# Pure_VCF.net
KiCad netlist of a schematic drawn in EAGLE
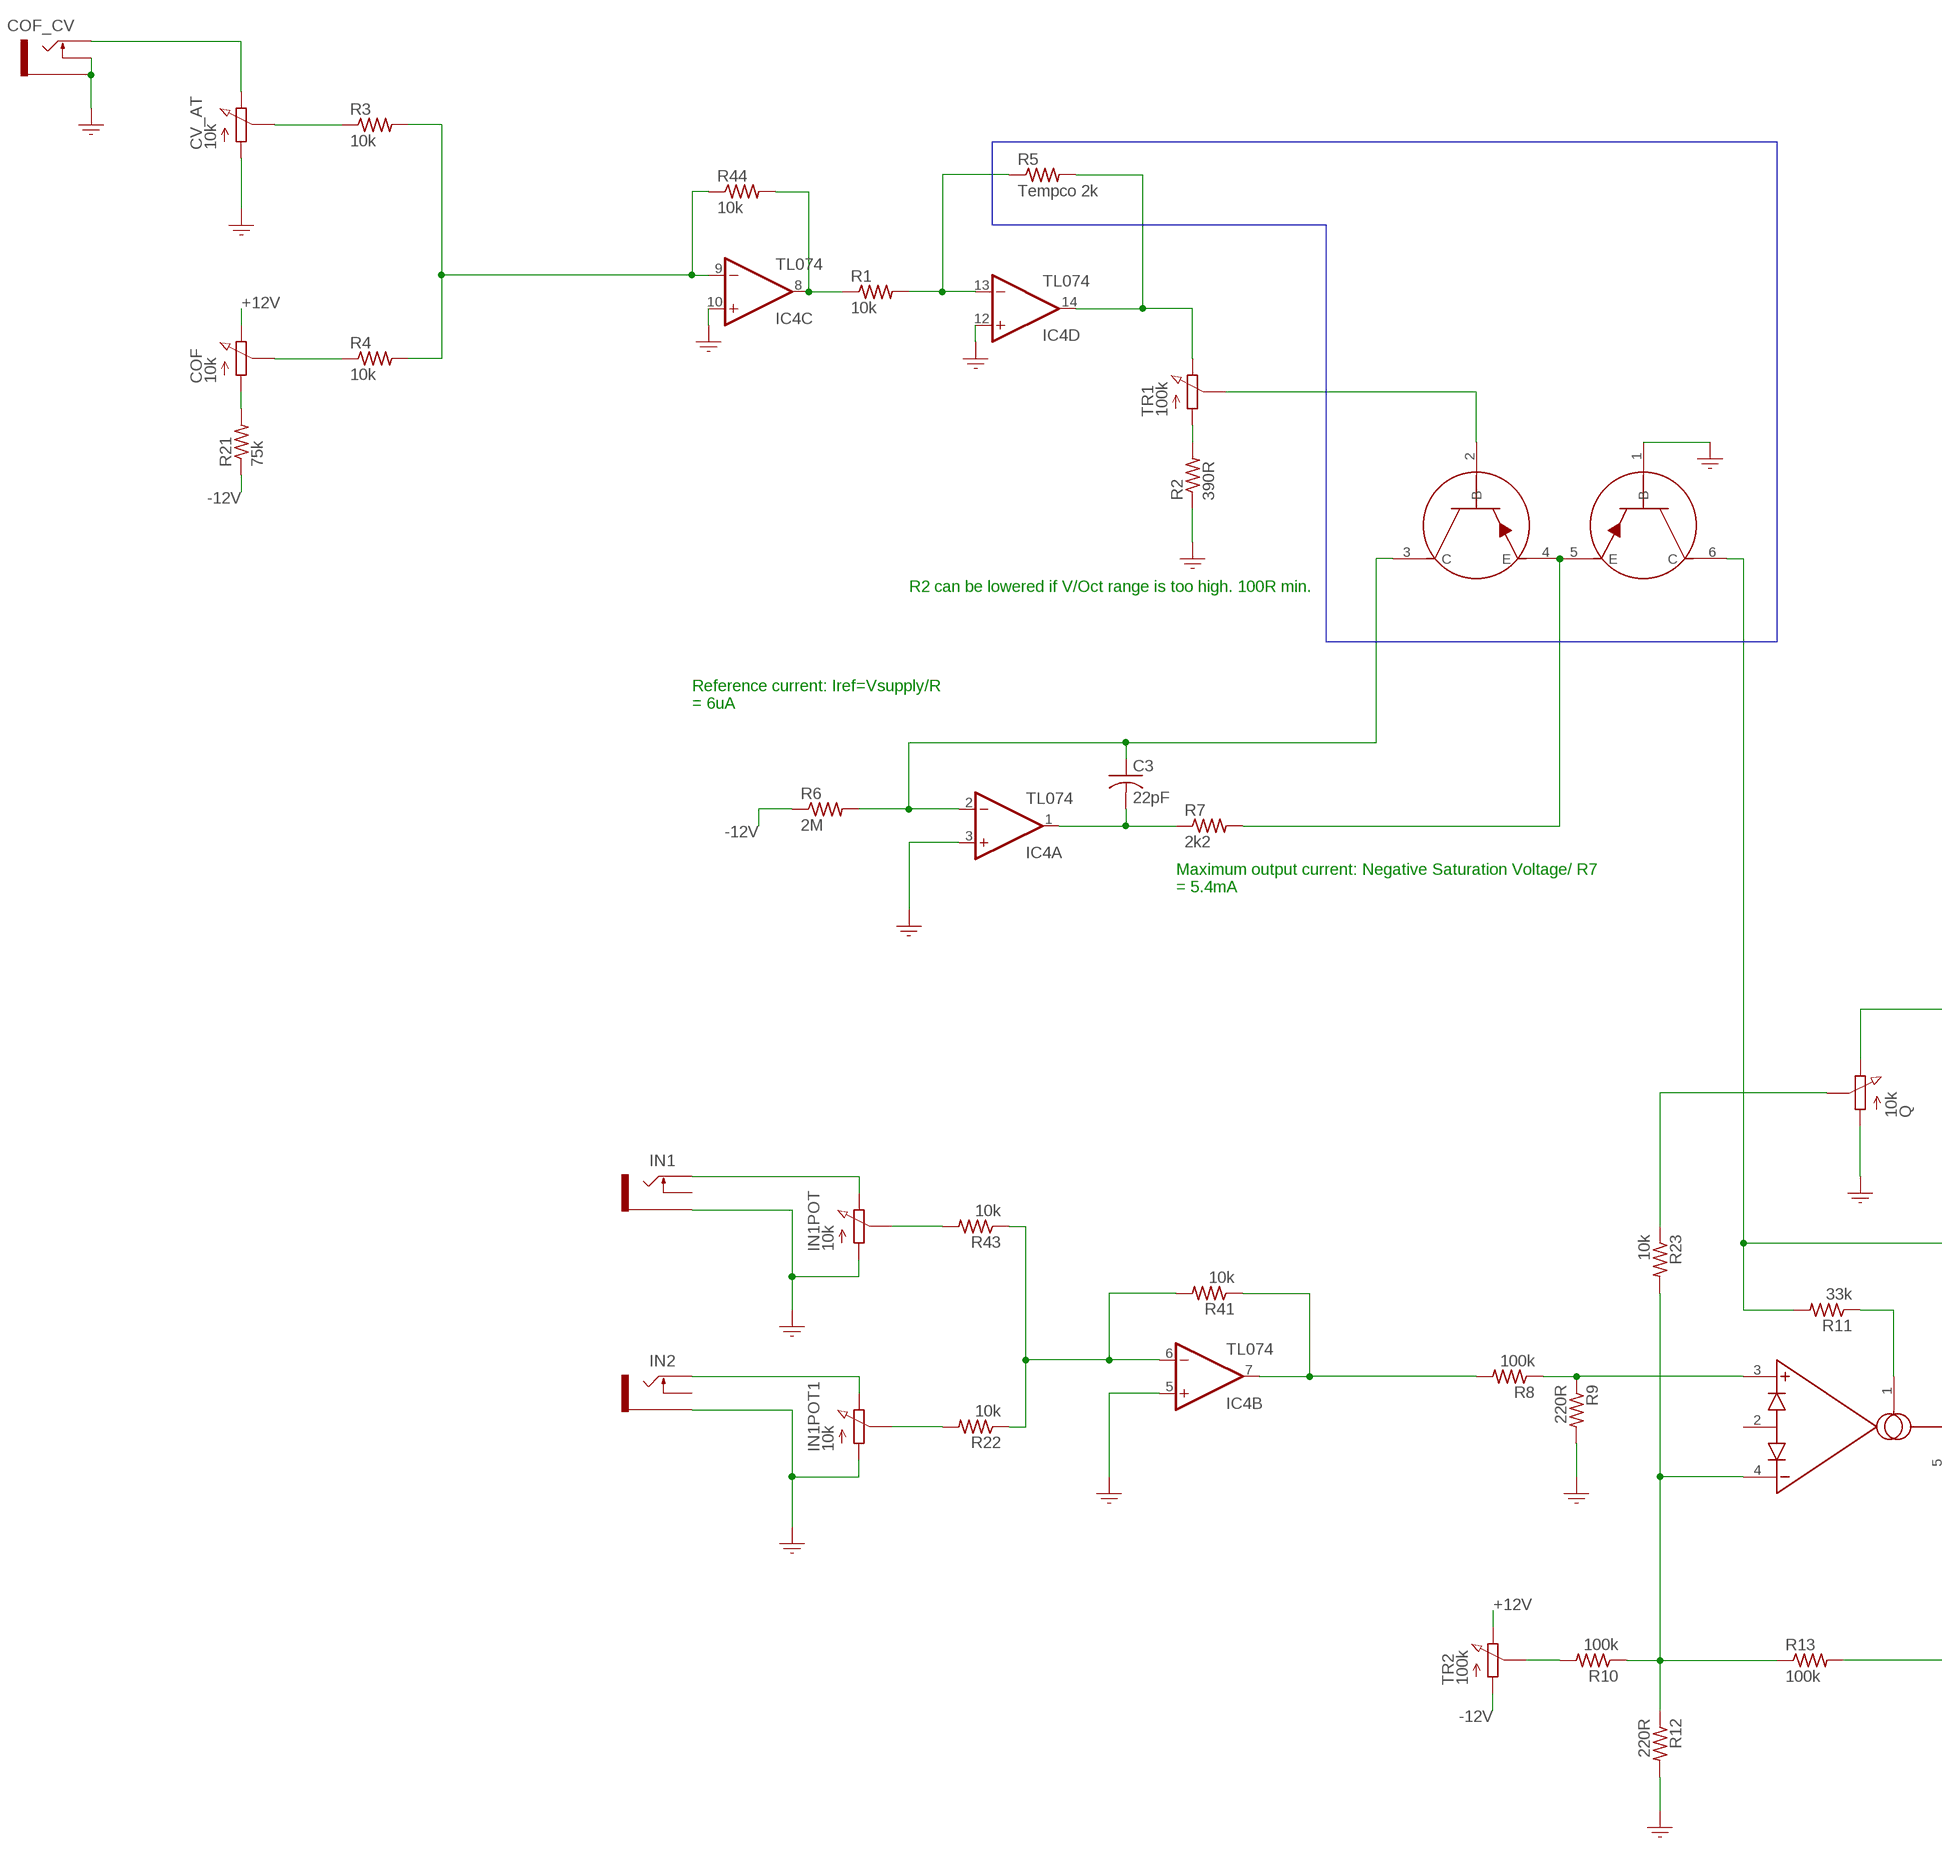
[diagram p0: schematic, sheet 1, part 1 of 2]
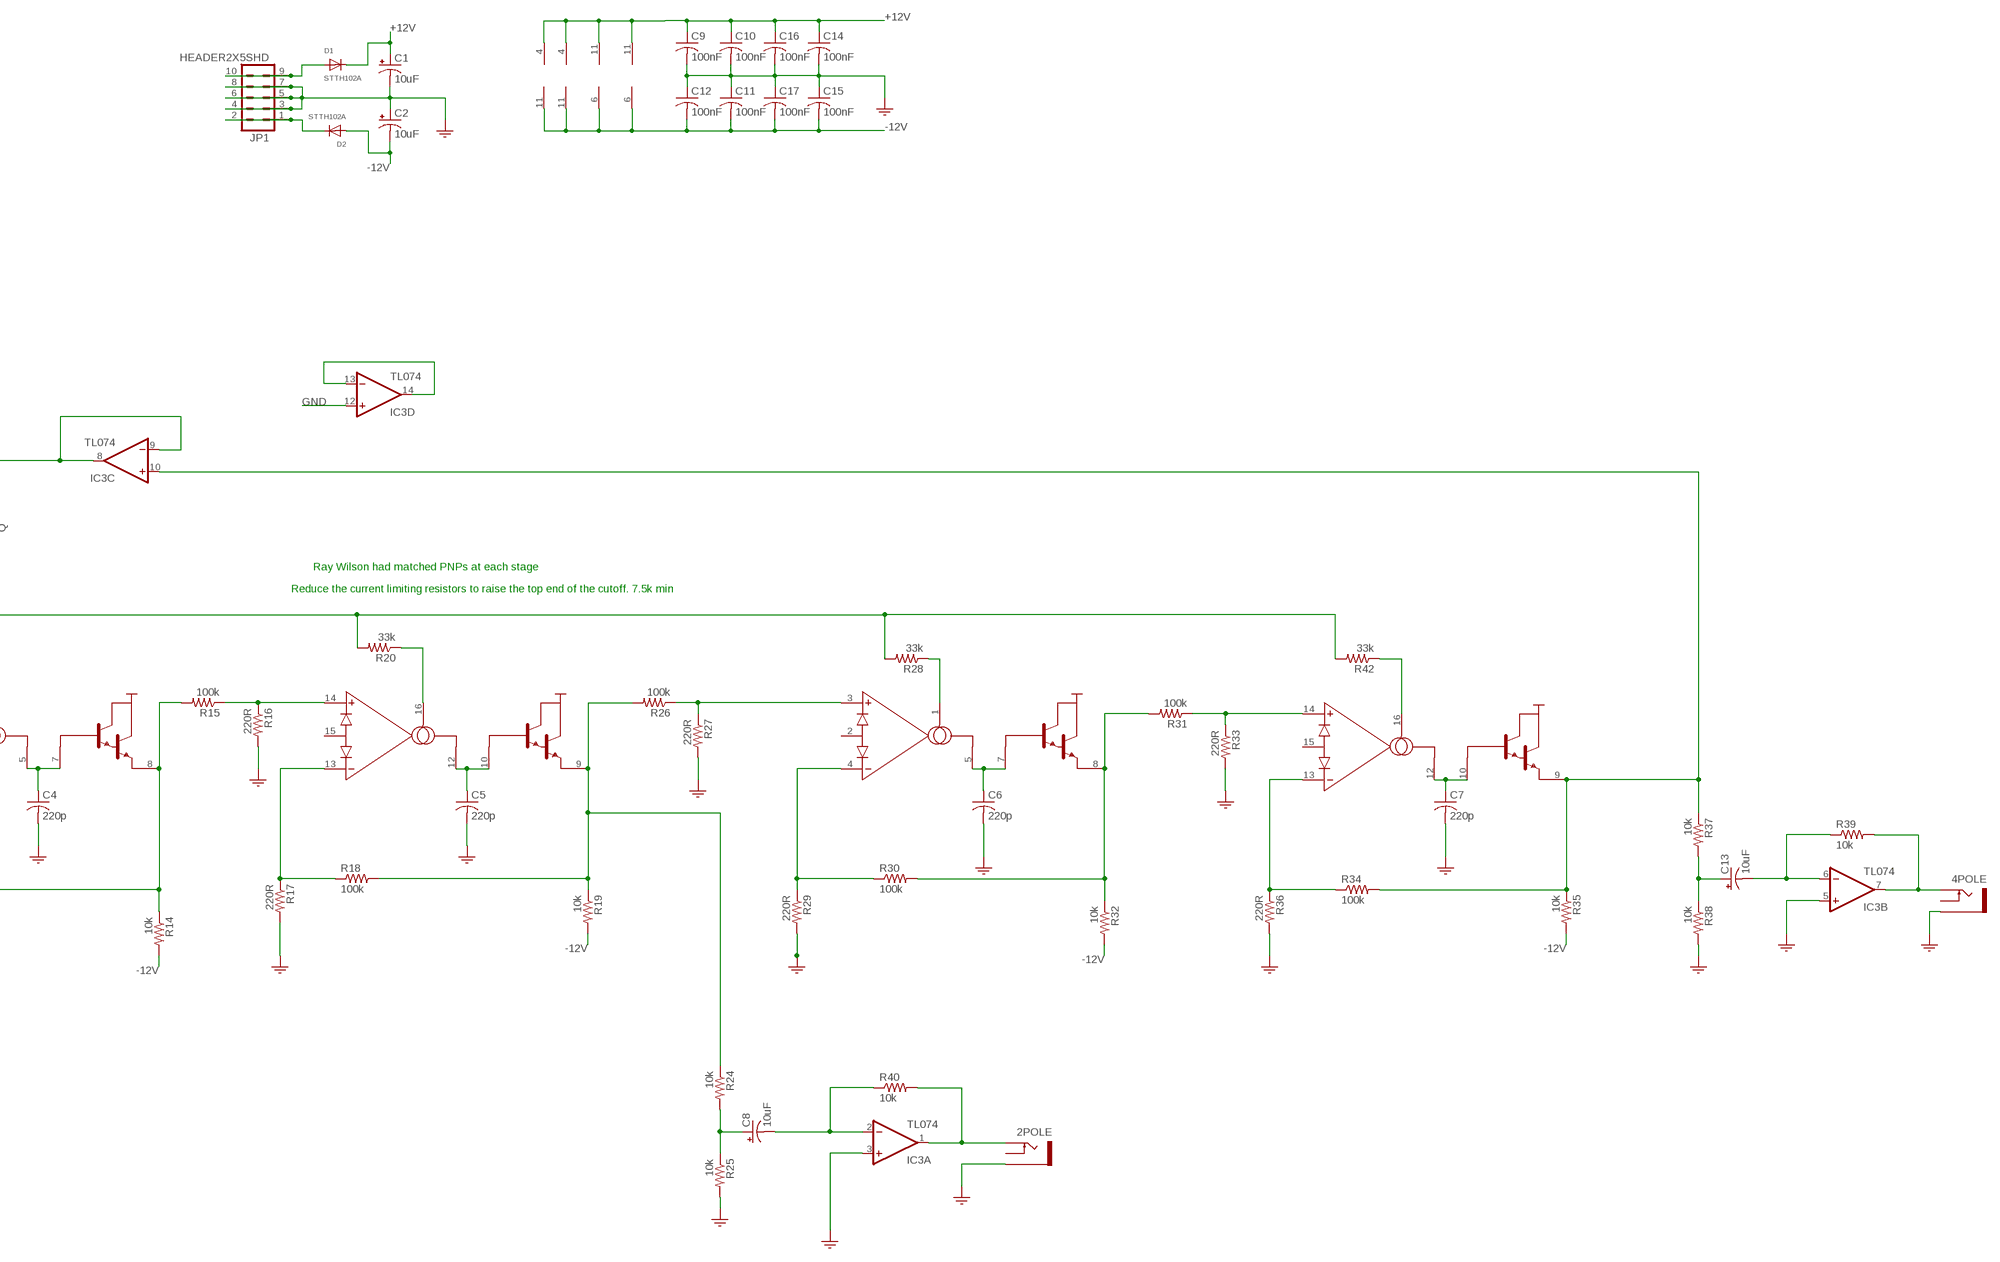
[diagram p1: schematic, sheet 1, part 2 of 2]

(export (version "E")
  (design (tool "Eeschema 10.0.6"))
  (components
    (comp (ref "2POLE")
      (value "PJ301M-12")
      (footprint "eagle-import:PJ301M-12")
      (libsource (lib "eagle-import") (part "SOCKET_MONO_3.5MMPJ301M-12"))
    )
    (comp (ref "4POLE")
      (value "PJ301M-12")
      (footprint "eagle-import:PJ301M-12")
      (libsource (lib "eagle-import") (part "SOCKET_MONO_3.5MMPJ301M-12"))
    )
    (comp (ref "C1")
      (value "10uF")
      (footprint "eagle-import:153CLV-0505")
      (libsource (lib "eagle-import") (part "CAPACITOR_POL-US153CLV-0505"))
    )
    (comp (ref "C2")
      (value "10uF")
      (footprint "eagle-import:153CLV-0505")
      (libsource (lib "eagle-import") (part "CAPACITOR_POL-US153CLV-0505"))
    )
    (comp (ref "C3")
      (value "22pF")
      (footprint "eagle-import:C0805")
      (libsource (lib "eagle-import") (part "CAPACITOR-USC0805"))
    )
    (comp (ref "C4")
      (value "220p")
      (footprint "eagle-import:C050-045X075")
      (libsource (lib "eagle-import") (part "CAPACITOR-USC050-045X075"))
    )
    (comp (ref "C5")
      (value "220p")
      (footprint "eagle-import:C050-045X075")
      (libsource (lib "eagle-import") (part "CAPACITOR-USC050-045X075"))
    )
    (comp (ref "C6")
      (value "220p")
      (footprint "eagle-import:C050-045X075")
      (libsource (lib "eagle-import") (part "CAPACITOR-USC050-045X075"))
    )
    (comp (ref "C7")
      (value "220p")
      (footprint "eagle-import:C050-045X075")
      (libsource (lib "eagle-import") (part "CAPACITOR-USC050-045X075"))
    )
    (comp (ref "C8")
      (value "10uF")
      (footprint "eagle-import:153CLV-0505")
      (libsource (lib "eagle-import") (part "CAPACITOR_POL-US153CLV-0505"))
    )
    (comp (ref "C9")
      (value "100nF")
      (footprint "eagle-import:C0805")
      (libsource (lib "eagle-import") (part "CAPACITOR-USC0805"))
    )
    (comp (ref "C10")
      (value "100nF")
      (footprint "eagle-import:C0805")
      (libsource (lib "eagle-import") (part "CAPACITOR-USC0805"))
    )
    (comp (ref "C11")
      (value "100nF")
      (footprint "eagle-import:C0805")
      (libsource (lib "eagle-import") (part "CAPACITOR-USC0805"))
    )
    (comp (ref "C12")
      (value "100nF")
      (footprint "eagle-import:C0805")
      (libsource (lib "eagle-import") (part "CAPACITOR-USC0805"))
    )
    (comp (ref "C13")
      (value "10uF")
      (footprint "eagle-import:153CLV-0505")
      (libsource (lib "eagle-import") (part "CAPACITOR_POL-US153CLV-0505"))
    )
    (comp (ref "C14")
      (value "100nF")
      (footprint "eagle-import:C0805")
      (libsource (lib "eagle-import") (part "CAPACITOR-USC0805"))
    )
    (comp (ref "C15")
      (value "100nF")
      (footprint "eagle-import:C0805")
      (libsource (lib "eagle-import") (part "CAPACITOR-USC0805"))
    )
    (comp (ref "C16")
      (value "100nF")
      (footprint "eagle-import:C0805")
      (libsource (lib "eagle-import") (part "CAPACITOR-USC0805"))
    )
    (comp (ref "C17")
      (value "100nF")
      (footprint "eagle-import:C0805")
      (libsource (lib "eagle-import") (part "CAPACITOR-USC0805"))
    )
    (comp (ref "COF")
      (value "10k")
      (footprint "eagle-import:POT_9MM_RED_KNOB")
      (libsource (lib "eagle-import") (part "RESISTOR_VARIABLEPOT_9MM_RED_KNOB"))
    )
    (comp (ref "COF_CV")
      (value "PJ301M-12")
      (footprint "eagle-import:PJ301M-12")
      (libsource (lib "eagle-import") (part "SOCKET_MONO_3.5MMPJ301M-12"))
    )
    (comp (ref "CV_AT")
      (value "10k")
      (footprint "eagle-import:POT_9MM_GREEN_KNOB")
      (libsource (lib "eagle-import") (part "RESISTOR_VARIABLEPOT_9MM_GREEN_KNOB"))
    )
    (comp (ref "D1")
      (value "STTH102A")
      (footprint "eagle-import:SMADIODE")
      (libsource (lib "eagle-import") (part "DIODESMA"))
    )
    (comp (ref "D2")
      (value "STTH102A")
      (footprint "eagle-import:SMADIODE")
      (libsource (lib "eagle-import") (part "DIODESMA"))
    )
    (comp (ref "IC1")
      (value "LM13700")
      (footprint "eagle-import:SOIC-16_BLANK")
      (libsource (lib "eagle-import") (part "OTA_LM13700"))
    )
    (comp (ref "IC2")
      (value "LM13700")
      (footprint "eagle-import:SOIC-16_BLANK")
      (libsource (lib "eagle-import") (part "OTA_LM13700"))
    )
    (comp (ref "IC3")
      (value "TL074")
      (footprint "eagle-import:SO14")
      (libsource (lib "eagle-import") (part "OPAMP_QUADD"))
    )
    (comp (ref "IC4")
      (value "TL074")
      (footprint "eagle-import:SO14")
      (libsource (lib "eagle-import") (part "OPAMP_QUADD"))
    )
    (comp (ref "IN1")
      (value "PJ301M-12")
      (footprint "eagle-import:PJ301M-12")
      (libsource (lib "eagle-import") (part "SOCKET_MONO_3.5MMPJ301M-12"))
    )
    (comp (ref "IN1POT")
      (value "10k")
      (footprint "eagle-import:POT_9MM_BLUE_KNOB")
      (libsource (lib "eagle-import") (part "RESISTOR_VARIABLEPOT_9MM_BLUE_KNOB"))
    )
    (comp (ref "IN1POT1")
      (value "10k")
      (footprint "eagle-import:POT_9MM_BLUE_KNOB")
      (libsource (lib "eagle-import") (part "RESISTOR_VARIABLEPOT_9MM_BLUE_KNOB"))
    )
    (comp (ref "IN2")
      (value "PJ301M-12")
      (footprint "eagle-import:PJ301M-12")
      (libsource (lib "eagle-import") (part "SOCKET_MONO_3.5MMPJ301M-12"))
    )
    (comp (ref "JP1")
      (value "HEADER2X5SHD")
      (footprint "eagle-import:2X5-SHROUDED")
      (libsource (lib "eagle-import") (part "HEADER2X5SHD"))
    )
    (comp (ref "Q")
      (value "10k")
      (footprint "eagle-import:POT_9MM_YELLOW_KNOB")
      (libsource (lib "eagle-import") (part "RESISTOR_VARIABLEPOT_9MM_YELLOW_KNOB"))
    )
    (comp (ref "R1")
      (value "10k")
      (footprint "eagle-import:R0805")
      (libsource (lib "eagle-import") (part "RESISTOR_USR0805"))
    )
    (comp (ref "R2")
      (value "390R")
      (footprint "eagle-import:R0805")
      (libsource (lib "eagle-import") (part "RESISTOR_USR0805"))
    )
    (comp (ref "R3")
      (value "10k")
      (footprint "eagle-import:R0805")
      (libsource (lib "eagle-import") (part "RESISTOR_USR0805"))
    )
    (comp (ref "R4")
      (value "10k")
      (footprint "eagle-import:R0805")
      (libsource (lib "eagle-import") (part "RESISTOR_USR0805"))
    )
    (comp (ref "R5")
      (value "Tempco 2k")
      (footprint "eagle-import:0207_8.5")
      (libsource (lib "eagle-import") (part "RESISTOR_US0207/8.5"))
    )
    (comp (ref "R6")
      (value "2M")
      (footprint "eagle-import:R0805")
      (libsource (lib "eagle-import") (part "RESISTOR_USR0805"))
    )
    (comp (ref "R7")
      (value "2k2")
      (footprint "eagle-import:R0805")
      (libsource (lib "eagle-import") (part "RESISTOR_USR0805"))
    )
    (comp (ref "R8")
      (value "100k")
      (footprint "eagle-import:R0805")
      (libsource (lib "eagle-import") (part "RESISTOR_USR0805"))
    )
    (comp (ref "R9")
      (value "220R")
      (footprint "eagle-import:R0805")
      (libsource (lib "eagle-import") (part "RESISTOR_USR0805"))
    )
    (comp (ref "R10")
      (value "100k")
      (footprint "eagle-import:R0805")
      (libsource (lib "eagle-import") (part "RESISTOR_USR0805"))
    )
    (comp (ref "R11")
      (value "33k")
      (footprint "eagle-import:R0805")
      (libsource (lib "eagle-import") (part "RESISTOR_USR0805"))
    )
    (comp (ref "R12")
      (value "220R")
      (footprint "eagle-import:R0805")
      (libsource (lib "eagle-import") (part "RESISTOR_USR0805"))
    )
    (comp (ref "R13")
      (value "100k")
      (footprint "eagle-import:R0805")
      (libsource (lib "eagle-import") (part "RESISTOR_USR0805"))
    )
    (comp (ref "R14")
      (value "10k")
      (footprint "eagle-import:R0805")
      (libsource (lib "eagle-import") (part "RESISTOR_USR0805"))
    )
    (comp (ref "R15")
      (value "100k")
      (footprint "eagle-import:R0805")
      (libsource (lib "eagle-import") (part "RESISTOR_USR0805"))
    )
    (comp (ref "R16")
      (value "220R")
      (footprint "eagle-import:R0805")
      (libsource (lib "eagle-import") (part "RESISTOR_USR0805"))
    )
    (comp (ref "R17")
      (value "220R")
      (footprint "eagle-import:R0805")
      (libsource (lib "eagle-import") (part "RESISTOR_USR0805"))
    )
    (comp (ref "R18")
      (value "100k")
      (footprint "eagle-import:R0805")
      (libsource (lib "eagle-import") (part "RESISTOR_USR0805"))
    )
    (comp (ref "R19")
      (value "10k")
      (footprint "eagle-import:R0805")
      (libsource (lib "eagle-import") (part "RESISTOR_USR0805"))
    )
    (comp (ref "R20")
      (value "33k")
      (footprint "eagle-import:R0805")
      (libsource (lib "eagle-import") (part "RESISTOR_USR0805"))
    )
    (comp (ref "R21")
      (value "75k")
      (footprint "eagle-import:R0805")
      (libsource (lib "eagle-import") (part "RESISTOR_USR0805"))
    )
    (comp (ref "R22")
      (value "10k")
      (footprint "eagle-import:R0805")
      (libsource (lib "eagle-import") (part "RESISTOR_USR0805"))
    )
    (comp (ref "R23")
      (value "10k")
      (footprint "eagle-import:R0805")
      (libsource (lib "eagle-import") (part "RESISTOR_USR0805"))
    )
    (comp (ref "R24")
      (value "10k")
      (footprint "eagle-import:R0805")
      (libsource (lib "eagle-import") (part "RESISTOR_USR0805"))
    )
    (comp (ref "R25")
      (value "10k")
      (footprint "eagle-import:R0805")
      (libsource (lib "eagle-import") (part "RESISTOR_USR0805"))
    )
    (comp (ref "R26")
      (value "100k")
      (footprint "eagle-import:R0805")
      (libsource (lib "eagle-import") (part "RESISTOR_USR0805"))
    )
    (comp (ref "R27")
      (value "220R")
      (footprint "eagle-import:R0805")
      (libsource (lib "eagle-import") (part "RESISTOR_USR0805"))
    )
    (comp (ref "R28")
      (value "33k")
      (footprint "eagle-import:R0805")
      (libsource (lib "eagle-import") (part "RESISTOR_USR0805"))
    )
    (comp (ref "R29")
      (value "220R")
      (footprint "eagle-import:R0805")
      (libsource (lib "eagle-import") (part "RESISTOR_USR0805"))
    )
    (comp (ref "R30")
      (value "100k")
      (footprint "eagle-import:R0805")
      (libsource (lib "eagle-import") (part "RESISTOR_USR0805"))
    )
    (comp (ref "R31")
      (value "100k")
      (footprint "eagle-import:R0805")
      (libsource (lib "eagle-import") (part "RESISTOR_USR0805"))
    )
    (comp (ref "R32")
      (value "10k")
      (footprint "eagle-import:R0805")
      (libsource (lib "eagle-import") (part "RESISTOR_USR0805"))
    )
    (comp (ref "R33")
      (value "220R")
      (footprint "eagle-import:R0805")
      (libsource (lib "eagle-import") (part "RESISTOR_USR0805"))
    )
    (comp (ref "R34")
      (value "100k")
      (footprint "eagle-import:R0805")
      (libsource (lib "eagle-import") (part "RESISTOR_USR0805"))
    )
    (comp (ref "R35")
      (value "10k")
      (footprint "eagle-import:R0805")
      (libsource (lib "eagle-import") (part "RESISTOR_USR0805"))
    )
    (comp (ref "R36")
      (value "220R")
      (footprint "eagle-import:R0805")
      (libsource (lib "eagle-import") (part "RESISTOR_USR0805"))
    )
    (comp (ref "R37")
      (value "10k")
      (footprint "eagle-import:R0805")
      (libsource (lib "eagle-import") (part "RESISTOR_USR0805"))
    )
    (comp (ref "R38")
      (value "10k")
      (footprint "eagle-import:R0805")
      (libsource (lib "eagle-import") (part "RESISTOR_USR0805"))
    )
    (comp (ref "R39")
      (value "10k")
      (footprint "eagle-import:R0805")
      (libsource (lib "eagle-import") (part "RESISTOR_USR0805"))
    )
    (comp (ref "R40")
      (value "10k")
      (footprint "eagle-import:R0805")
      (libsource (lib "eagle-import") (part "RESISTOR_USR0805"))
    )
    (comp (ref "R41")
      (value "10k")
      (footprint "eagle-import:R0805")
      (libsource (lib "eagle-import") (part "RESISTOR_USR0805"))
    )
    (comp (ref "R42")
      (value "33k")
      (footprint "eagle-import:R0805")
      (libsource (lib "eagle-import") (part "RESISTOR_USR0805"))
    )
    (comp (ref "R43")
      (value "10k")
      (footprint "eagle-import:R0805")
      (libsource (lib "eagle-import") (part "RESISTOR_USR0805"))
    )
    (comp (ref "R44")
      (value "10k")
      (footprint "eagle-import:R0805")
      (libsource (lib "eagle-import") (part "RESISTOR_USR0805"))
    )
    (comp (ref "T1")
      (value "DMMT3906W")
      (footprint "eagle-import:TRANS_PAIR")
      (libsource (lib "eagle-import") (part "TRANSISTOR_PAIR_PNP"))
    )
    (comp (ref "TR1")
      (value "100k")
      (footprint "eagle-import:TRIMMER_TH")
      (libsource (lib "eagle-import") (part "RESISTOR_VARIABLETRIMMER_TH"))
    )
    (comp (ref "TR2")
      (value "100k")
      (footprint "eagle-import:TRIMMER_TH")
      (libsource (lib "eagle-import") (part "RESISTOR_VARIABLETRIMMER_TH"))
    )
  )
  (nets
    (net (code "1") (name "/+12V") (class "Default")
      (node (ref "C1") (pin "+") (pinfunction "+_+") (pintype "passive"))
      (node (ref "C10") (pin "1") (pinfunction "1_1") (pintype "passive"))
      (node (ref "C14") (pin "1") (pinfunction "1_1") (pintype "passive"))
      (node (ref "C16") (pin "1") (pinfunction "1_1") (pintype "passive"))
      (node (ref "C9") (pin "1") (pinfunction "1_1") (pintype "passive"))
      (node (ref "COF") (pin "P$3") (pinfunction "3_P$3") (pintype "passive"))
      (node (ref "D1") (pin "C") (pinfunction "C_C") (pintype "passive"))
      (node (ref "IC1") (pin "11") (pinfunction "V+_11") (pintype "power_in"))
      (node (ref "IC2") (pin "11") (pinfunction "V+_11") (pintype "power_in"))
      (node (ref "IC3") (pin "4") (pinfunction "V+_4") (pintype "power_in"))
      (node (ref "IC4") (pin "4") (pinfunction "V+_4") (pintype "power_in"))
      (node (ref "TR2") (pin "3") (pinfunction "3_3") (pintype "passive"))
    )
    (net (code "2") (name "/-12V") (class "Default")
      (node (ref "C11") (pin "2") (pinfunction "2_2") (pintype "passive"))
      (node (ref "C12") (pin "2") (pinfunction "2_2") (pintype "passive"))
      (node (ref "C15") (pin "2") (pinfunction "2_2") (pintype "passive"))
      (node (ref "C17") (pin "2") (pinfunction "2_2") (pintype "passive"))
      (node (ref "C2") (pin "-") (pinfunction "-_-") (pintype "passive"))
      (node (ref "D2") (pin "A") (pinfunction "A_A") (pintype "passive"))
      (node (ref "IC1") (pin "6") (pinfunction "V-_6") (pintype "power_in"))
      (node (ref "IC2") (pin "6") (pinfunction "V-_6") (pintype "power_in"))
      (node (ref "IC3") (pin "11") (pinfunction "V-_11") (pintype "power_in"))
      (node (ref "IC4") (pin "11") (pinfunction "V-_11") (pintype "power_in"))
      (node (ref "R14") (pin "2") (pinfunction "2_2") (pintype "passive"))
      (node (ref "R19") (pin "2") (pinfunction "2_2") (pintype "passive"))
      (node (ref "R21") (pin "1") (pinfunction "1_1") (pintype "passive"))
      (node (ref "R32") (pin "2") (pinfunction "2_2") (pintype "passive"))
      (node (ref "R35") (pin "2") (pinfunction "2_2") (pintype "passive"))
      (node (ref "R6") (pin "1") (pinfunction "1_1") (pintype "passive"))
      (node (ref "TR2") (pin "1") (pinfunction "1_1") (pintype "passive"))
    )
    (net (code "3") (name "GND") (class "Default")
      (node (ref "2POLE") (pin "GND") (pinfunction "SLEEVE_GND") (pintype "passive"))
      (node (ref "4POLE") (pin "GND") (pinfunction "SLEEVE_GND") (pintype "passive"))
      (node (ref "C1") (pin "-") (pinfunction "-_-") (pintype "passive"))
      (node (ref "C10") (pin "2") (pinfunction "2_2") (pintype "passive"))
      (node (ref "C11") (pin "1") (pinfunction "1_1") (pintype "passive"))
      (node (ref "C12") (pin "1") (pinfunction "1_1") (pintype "passive"))
      (node (ref "C14") (pin "2") (pinfunction "2_2") (pintype "passive"))
      (node (ref "C15") (pin "1") (pinfunction "1_1") (pintype "passive"))
      (node (ref "C16") (pin "2") (pinfunction "2_2") (pintype "passive"))
      (node (ref "C17") (pin "1") (pinfunction "1_1") (pintype "passive"))
      (node (ref "C2") (pin "+") (pinfunction "+_+") (pintype "passive"))
      (node (ref "C4") (pin "2") (pinfunction "2_2") (pintype "passive"))
      (node (ref "C5") (pin "2") (pinfunction "2_2") (pintype "passive"))
      (node (ref "C6") (pin "2") (pinfunction "2_2") (pintype "passive"))
      (node (ref "C7") (pin "2") (pinfunction "2_2") (pintype "passive"))
      (node (ref "C9") (pin "2") (pinfunction "2_2") (pintype "passive"))
      (node (ref "COF_CV") (pin "GND") (pinfunction "SLEEVE_GND") (pintype "passive"))
      (node (ref "COF_CV") (pin "NORM") (pinfunction "SWITCH_NORM") (pintype "passive"))
      (node (ref "CV_AT") (pin "P$1") (pinfunction "1_P$1") (pintype "passive"))
      (node (ref "IC3") (pin "12") (pinfunction "+IN_12") (pintype "input"))
      (node (ref "IC3") (pin "3") (pinfunction "+IN_3") (pintype "input"))
      (node (ref "IC3") (pin "5") (pinfunction "+IN_5") (pintype "input"))
      (node (ref "IC4") (pin "10") (pinfunction "+IN_10") (pintype "input"))
      (node (ref "IC4") (pin "12") (pinfunction "+IN_12") (pintype "input"))
      (node (ref "IC4") (pin "3") (pinfunction "+IN_3") (pintype "input"))
      (node (ref "IC4") (pin "5") (pinfunction "+IN_5") (pintype "input"))
      (node (ref "IN1") (pin "GND") (pinfunction "SLEEVE_GND") (pintype "passive"))
      (node (ref "IN1POT") (pin "P$1") (pinfunction "1_P$1") (pintype "passive"))
      (node (ref "IN1POT1") (pin "P$1") (pinfunction "1_P$1") (pintype "passive"))
      (node (ref "IN2") (pin "GND") (pinfunction "SLEEVE_GND") (pintype "passive"))
      (node (ref "JP1") (pin "3") (pinfunction "3_3") (pintype "passive"))
      (node (ref "JP1") (pin "4") (pinfunction "4_4") (pintype "passive"))
      (node (ref "JP1") (pin "5") (pinfunction "5_5") (pintype "passive"))
      (node (ref "JP1") (pin "6") (pinfunction "6_6") (pintype "passive"))
      (node (ref "JP1") (pin "7") (pinfunction "7_7") (pintype "passive"))
      (node (ref "JP1") (pin "8") (pinfunction "8_8") (pintype "passive"))
      (node (ref "Q") (pin "P$1") (pinfunction "1_P$1") (pintype "passive"))
      (node (ref "R12") (pin "2") (pinfunction "2_2") (pintype "passive"))
      (node (ref "R16") (pin "2") (pinfunction "2_2") (pintype "passive"))
      (node (ref "R17") (pin "2") (pinfunction "2_2") (pintype "passive"))
      (node (ref "R2") (pin "1") (pinfunction "1_1") (pintype "passive"))
      (node (ref "R25") (pin "2") (pinfunction "2_2") (pintype "passive"))
      (node (ref "R27") (pin "2") (pinfunction "2_2") (pintype "passive"))
      (node (ref "R29") (pin "2") (pinfunction "2_2") (pintype "passive"))
      (node (ref "R33") (pin "2") (pinfunction "2_2") (pintype "passive"))
      (node (ref "R36") (pin "2") (pinfunction "2_2") (pintype "passive"))
      (node (ref "R38") (pin "2") (pinfunction "2_2") (pintype "passive"))
      (node (ref "R9") (pin "2") (pinfunction "2_2") (pintype "passive"))
      (node (ref "T1") (pin "1") (pinfunction "B_1") (pintype "bidirectional"))
    )
    (net (code "4") (name "Net-(C8-Pad+)") (class "Default")
      (node (ref "C8") (pin "+") (pinfunction "+_+") (pintype "passive"))
      (node (ref "R24") (pin "2") (pinfunction "2_2") (pintype "passive"))
      (node (ref "R25") (pin "1") (pinfunction "1_1") (pintype "passive"))
    )
    (net (code "5") (name "Net-(C13-Pad+)") (class "Default")
      (node (ref "C13") (pin "+") (pinfunction "+_+") (pintype "passive"))
      (node (ref "R37") (pin "2") (pinfunction "2_2") (pintype "passive"))
      (node (ref "R38") (pin "1") (pinfunction "1_1") (pintype "passive"))
    )
    (net (code "6") (name "Net-(COF-1)") (class "Default")
      (node (ref "COF") (pin "P$1") (pinfunction "1_P$1") (pintype "passive"))
      (node (ref "R21") (pin "2") (pinfunction "2_2") (pintype "passive"))
    )
    (net (code "7") (name "Net-(COF-2)") (class "Default")
      (node (ref "COF") (pin "P$2") (pinfunction "2_P$2") (pintype "passive"))
      (node (ref "R4") (pin "1") (pinfunction "1_1") (pintype "passive"))
    )
    (net (code "8") (name "Net-(CV_AT-2)") (class "Default")
      (node (ref "CV_AT") (pin "P$2") (pinfunction "2_P$2") (pintype "passive"))
      (node (ref "R3") (pin "1") (pinfunction "1_1") (pintype "passive"))
    )
    (net (code "9") (name "Net-(CV_AT-3)") (class "Default")
      (node (ref "COF_CV") (pin "TIP") (pinfunction "TIP_TIP") (pintype "passive"))
      (node (ref "CV_AT") (pin "P$3") (pinfunction "3_P$3") (pintype "passive"))
    )
    (net (code "10") (name "Net-(D1-PadA)") (class "Default")
      (node (ref "D1") (pin "A") (pinfunction "A_A") (pintype "passive"))
      (node (ref "JP1") (pin "10") (pinfunction "10_10") (pintype "passive"))
      (node (ref "JP1") (pin "9") (pinfunction "9_9") (pintype "passive"))
    )
    (net (code "11") (name "Net-(D2-PadC)") (class "Default")
      (node (ref "D2") (pin "C") (pinfunction "C_C") (pintype "passive"))
      (node (ref "JP1") (pin "1") (pinfunction "1_1") (pintype "passive"))
      (node (ref "JP1") (pin "2") (pinfunction "2_2") (pintype "passive"))
    )
    (net (code "12") (name "Net-(IC1A-BIAS-IN)") (class "Default")
      (node (ref "IC1") (pin "1") (pinfunction "BIAS-IN_1") (pintype "bidirectional"))
      (node (ref "R11") (pin "1") (pinfunction "1_1") (pintype "passive"))
    )
    (net (code "13") (name "Net-(IC1A-BUF-IN_2)") (class "Default")
      (node (ref "C4") (pin "1") (pinfunction "1_1") (pintype "passive"))
      (node (ref "IC1") (pin "5") (pinfunction "OUT_5") (pintype "bidirectional"))
      (node (ref "IC1") (pin "7") (pinfunction "BUF-IN_2_7") (pintype "bidirectional"))
    )
    (net (code "14") (name "Net-(IC1A-BUF-OUT_2)") (class "Default")
      (node (ref "IC1") (pin "8") (pinfunction "BUF-OUT_2_8") (pintype "bidirectional"))
      (node (ref "R13") (pin "2") (pinfunction "2_2") (pintype "passive"))
      (node (ref "R14") (pin "1") (pinfunction "1_1") (pintype "passive"))
      (node (ref "R15") (pin "2") (pinfunction "2_2") (pintype "passive"))
    )
    (net (code "15") (name "Net-(IC1A-IN+)") (class "Default")
      (node (ref "IC1") (pin "3") (pinfunction "IN+_3") (pintype "bidirectional"))
      (node (ref "R8") (pin "1") (pinfunction "1_1") (pintype "passive"))
      (node (ref "R9") (pin "1") (pinfunction "1_1") (pintype "passive"))
    )
    (net (code "16") (name "Net-(IC1A-IN-)") (class "Default")
      (node (ref "IC1") (pin "4") (pinfunction "IN-_4") (pintype "bidirectional"))
      (node (ref "R10") (pin "1") (pinfunction "1_1") (pintype "passive"))
      (node (ref "R12") (pin "1") (pinfunction "1_1") (pintype "passive"))
      (node (ref "R13") (pin "1") (pinfunction "1_1") (pintype "passive"))
      (node (ref "R23") (pin "2") (pinfunction "2_2") (pintype "passive"))
    )
    (net (code "17") (name "Net-(IC1B-BIAS-IN)") (class "Default")
      (node (ref "IC1") (pin "16") (pinfunction "BIAS-IN_16") (pintype "bidirectional"))
      (node (ref "R20") (pin "1") (pinfunction "1_1") (pintype "passive"))
    )
    (net (code "18") (name "Net-(IC1B-BUF-IN_2)") (class "Default")
      (node (ref "C5") (pin "1") (pinfunction "1_1") (pintype "passive"))
      (node (ref "IC1") (pin "10") (pinfunction "BUF-IN_2_10") (pintype "bidirectional"))
      (node (ref "IC1") (pin "12") (pinfunction "OUT_12") (pintype "bidirectional"))
    )
    (net (code "19") (name "Net-(IC1B-BUF-OUT_2)") (class "Default")
      (node (ref "IC1") (pin "9") (pinfunction "BUF-OUT_2_9") (pintype "bidirectional"))
      (node (ref "R18") (pin "2") (pinfunction "2_2") (pintype "passive"))
      (node (ref "R19") (pin "1") (pinfunction "1_1") (pintype "passive"))
      (node (ref "R24") (pin "1") (pinfunction "1_1") (pintype "passive"))
      (node (ref "R26") (pin "2") (pinfunction "2_2") (pintype "passive"))
    )
    (net (code "20") (name "Net-(IC1B-IN+)") (class "Default")
      (node (ref "IC1") (pin "14") (pinfunction "IN+_14") (pintype "bidirectional"))
      (node (ref "R15") (pin "1") (pinfunction "1_1") (pintype "passive"))
      (node (ref "R16") (pin "1") (pinfunction "1_1") (pintype "passive"))
    )
    (net (code "21") (name "Net-(IC1B-IN-)") (class "Default")
      (node (ref "IC1") (pin "13") (pinfunction "IN-_13") (pintype "bidirectional"))
      (node (ref "R17") (pin "1") (pinfunction "1_1") (pintype "passive"))
      (node (ref "R18") (pin "1") (pinfunction "1_1") (pintype "passive"))
    )
    (net (code "22") (name "Net-(IC2A-BIAS-IN)") (class "Default")
      (node (ref "IC2") (pin "1") (pinfunction "BIAS-IN_1") (pintype "bidirectional"))
      (node (ref "R28") (pin "1") (pinfunction "1_1") (pintype "passive"))
    )
    (net (code "23") (name "Net-(IC2A-BUF-IN_2)") (class "Default")
      (node (ref "C6") (pin "1") (pinfunction "1_1") (pintype "passive"))
      (node (ref "IC2") (pin "5") (pinfunction "OUT_5") (pintype "bidirectional"))
      (node (ref "IC2") (pin "7") (pinfunction "BUF-IN_2_7") (pintype "bidirectional"))
    )
    (net (code "24") (name "Net-(IC2A-BUF-OUT_2)") (class "Default")
      (node (ref "IC2") (pin "8") (pinfunction "BUF-OUT_2_8") (pintype "bidirectional"))
      (node (ref "R30") (pin "2") (pinfunction "2_2") (pintype "passive"))
      (node (ref "R31") (pin "2") (pinfunction "2_2") (pintype "passive"))
      (node (ref "R32") (pin "1") (pinfunction "1_1") (pintype "passive"))
    )
    (net (code "25") (name "Net-(IC2A-IN+)") (class "Default")
      (node (ref "IC2") (pin "3") (pinfunction "IN+_3") (pintype "bidirectional"))
      (node (ref "R26") (pin "1") (pinfunction "1_1") (pintype "passive"))
      (node (ref "R27") (pin "1") (pinfunction "1_1") (pintype "passive"))
    )
    (net (code "26") (name "Net-(IC2A-IN-)") (class "Default")
      (node (ref "IC2") (pin "4") (pinfunction "IN-_4") (pintype "bidirectional"))
      (node (ref "R29") (pin "1") (pinfunction "1_1") (pintype "passive"))
      (node (ref "R30") (pin "1") (pinfunction "1_1") (pintype "passive"))
    )
    (net (code "27") (name "Net-(IC2B-BIAS-IN)") (class "Default")
      (node (ref "IC2") (pin "16") (pinfunction "BIAS-IN_16") (pintype "bidirectional"))
      (node (ref "R42") (pin "1") (pinfunction "1_1") (pintype "passive"))
    )
    (net (code "28") (name "Net-(IC2B-BUF-IN_2)") (class "Default")
      (node (ref "C7") (pin "1") (pinfunction "1_1") (pintype "passive"))
      (node (ref "IC2") (pin "10") (pinfunction "BUF-IN_2_10") (pintype "bidirectional"))
      (node (ref "IC2") (pin "12") (pinfunction "OUT_12") (pintype "bidirectional"))
    )
    (net (code "29") (name "Net-(IC2B-BUF-OUT_2)") (class "Default")
      (node (ref "IC2") (pin "9") (pinfunction "BUF-OUT_2_9") (pintype "bidirectional"))
      (node (ref "IC3") (pin "10") (pinfunction "+IN_10") (pintype "input"))
      (node (ref "R34") (pin "2") (pinfunction "2_2") (pintype "passive"))
      (node (ref "R35") (pin "1") (pinfunction "1_1") (pintype "passive"))
      (node (ref "R37") (pin "1") (pinfunction "1_1") (pintype "passive"))
    )
    (net (code "30") (name "Net-(IC2B-IN+)") (class "Default")
      (node (ref "IC2") (pin "14") (pinfunction "IN+_14") (pintype "bidirectional"))
      (node (ref "R31") (pin "1") (pinfunction "1_1") (pintype "passive"))
      (node (ref "R33") (pin "1") (pinfunction "1_1") (pintype "passive"))
    )
    (net (code "31") (name "Net-(IC2B-IN-)") (class "Default")
      (node (ref "IC2") (pin "13") (pinfunction "IN-_13") (pintype "bidirectional"))
      (node (ref "R34") (pin "1") (pinfunction "1_1") (pintype "passive"))
      (node (ref "R36") (pin "1") (pinfunction "1_1") (pintype "passive"))
    )
    (net (code "32") (name "Net-(IC3A--IN)") (class "Default")
      (node (ref "C8") (pin "-") (pinfunction "-_-") (pintype "passive"))
      (node (ref "IC3") (pin "2") (pinfunction "-IN_2") (pintype "input"))
      (node (ref "R40") (pin "1") (pinfunction "1_1") (pintype "passive"))
    )
    (net (code "33") (name "Net-(IC3A-OUT)") (class "Default")
      (node (ref "2POLE") (pin "TIP") (pinfunction "TIP_TIP") (pintype "passive"))
      (node (ref "IC3") (pin "1") (pinfunction "OUT_1") (pintype "output"))
      (node (ref "R40") (pin "2") (pinfunction "2_2") (pintype "passive"))
    )
    (net (code "34") (name "Net-(IC3B--IN)") (class "Default")
      (node (ref "C13") (pin "-") (pinfunction "-_-") (pintype "passive"))
      (node (ref "IC3") (pin "6") (pinfunction "-IN_6") (pintype "input"))
      (node (ref "R39") (pin "1") (pinfunction "1_1") (pintype "passive"))
    )
    (net (code "35") (name "Net-(IC3B-OUT)") (class "Default")
      (node (ref "4POLE") (pin "TIP") (pinfunction "TIP_TIP") (pintype "passive"))
      (node (ref "IC3") (pin "7") (pinfunction "OUT_7") (pintype "output"))
      (node (ref "R39") (pin "2") (pinfunction "2_2") (pintype "passive"))
    )
    (net (code "36") (name "Net-(IC3C--IN)") (class "Default")
      (node (ref "IC3") (pin "8") (pinfunction "OUT_8") (pintype "output"))
      (node (ref "IC3") (pin "9") (pinfunction "-IN_9") (pintype "input"))
      (node (ref "Q") (pin "P$3") (pinfunction "3_P$3") (pintype "passive"))
    )
    (net (code "37") (name "Net-(IC3D--IN)") (class "Default")
      (node (ref "IC3") (pin "13") (pinfunction "-IN_13") (pintype "input"))
      (node (ref "IC3") (pin "14") (pinfunction "OUT_14") (pintype "output"))
    )
    (net (code "38") (name "Net-(IC4A--IN)") (class "Default")
      (node (ref "C3") (pin "1") (pinfunction "1_1") (pintype "passive"))
      (node (ref "IC4") (pin "2") (pinfunction "-IN_2") (pintype "input"))
      (node (ref "R6") (pin "2") (pinfunction "2_2") (pintype "passive"))
      (node (ref "T1") (pin "3") (pinfunction "C_3") (pintype "bidirectional"))
    )
    (net (code "39") (name "Net-(IC4A-OUT)") (class "Default")
      (node (ref "C3") (pin "2") (pinfunction "2_2") (pintype "passive"))
      (node (ref "IC4") (pin "1") (pinfunction "OUT_1") (pintype "output"))
      (node (ref "R7") (pin "1") (pinfunction "1_1") (pintype "passive"))
    )
    (net (code "40") (name "Net-(IC4B--IN)") (class "Default")
      (node (ref "IC4") (pin "6") (pinfunction "-IN_6") (pintype "input"))
      (node (ref "R22") (pin "1") (pinfunction "1_1") (pintype "passive"))
      (node (ref "R41") (pin "2") (pinfunction "2_2") (pintype "passive"))
      (node (ref "R43") (pin "1") (pinfunction "1_1") (pintype "passive"))
    )
    (net (code "41") (name "Net-(IC4B-OUT)") (class "Default")
      (node (ref "IC4") (pin "7") (pinfunction "OUT_7") (pintype "output"))
      (node (ref "R41") (pin "1") (pinfunction "1_1") (pintype "passive"))
      (node (ref "R8") (pin "2") (pinfunction "2_2") (pintype "passive"))
    )
    (net (code "42") (name "Net-(IC4C--IN)") (class "Default")
      (node (ref "IC4") (pin "9") (pinfunction "-IN_9") (pintype "input"))
      (node (ref "R3") (pin "2") (pinfunction "2_2") (pintype "passive"))
      (node (ref "R4") (pin "2") (pinfunction "2_2") (pintype "passive"))
      (node (ref "R44") (pin "1") (pinfunction "1_1") (pintype "passive"))
    )
    (net (code "43") (name "Net-(IC4C-OUT)") (class "Default")
      (node (ref "IC4") (pin "8") (pinfunction "OUT_8") (pintype "output"))
      (node (ref "R1") (pin "1") (pinfunction "1_1") (pintype "passive"))
      (node (ref "R44") (pin "2") (pinfunction "2_2") (pintype "passive"))
    )
    (net (code "44") (name "Net-(IC4D--IN)") (class "Default")
      (node (ref "IC4") (pin "13") (pinfunction "-IN_13") (pintype "input"))
      (node (ref "R1") (pin "2") (pinfunction "2_2") (pintype "passive"))
      (node (ref "R5") (pin "1") (pinfunction "1_1") (pintype "passive"))
    )
    (net (code "45") (name "Net-(IC4D-OUT)") (class "Default")
      (node (ref "IC4") (pin "14") (pinfunction "OUT_14") (pintype "output"))
      (node (ref "R5") (pin "2") (pinfunction "2_2") (pintype "passive"))
      (node (ref "TR1") (pin "3") (pinfunction "3_3") (pintype "passive"))
    )
    (net (code "46") (name "Net-(IN1POT-2)") (class "Default")
      (node (ref "IN1POT") (pin "P$2") (pinfunction "2_P$2") (pintype "passive"))
      (node (ref "R43") (pin "2") (pinfunction "2_2") (pintype "passive"))
    )
    (net (code "47") (name "Net-(IN1POT-3)") (class "Default")
      (node (ref "IN1") (pin "TIP") (pinfunction "TIP_TIP") (pintype "passive"))
      (node (ref "IN1POT") (pin "P$3") (pinfunction "3_P$3") (pintype "passive"))
    )
    (net (code "48") (name "Net-(IN1POT1-2)") (class "Default")
      (node (ref "IN1POT1") (pin "P$2") (pinfunction "2_P$2") (pintype "passive"))
      (node (ref "R22") (pin "2") (pinfunction "2_2") (pintype "passive"))
    )
    (net (code "49") (name "Net-(IN1POT1-3)") (class "Default")
      (node (ref "IN1POT1") (pin "P$3") (pinfunction "3_P$3") (pintype "passive"))
      (node (ref "IN2") (pin "TIP") (pinfunction "TIP_TIP") (pintype "passive"))
    )
    (net (code "50") (name "Net-(Q-2)") (class "Default")
      (node (ref "Q") (pin "P$2") (pinfunction "2_P$2") (pintype "passive"))
      (node (ref "R23") (pin "1") (pinfunction "1_1") (pintype "passive"))
    )
    (net (code "51") (name "Net-(R2-Pad2)") (class "Default")
      (node (ref "R2") (pin "2") (pinfunction "2_2") (pintype "passive"))
      (node (ref "TR1") (pin "1") (pinfunction "1_1") (pintype "passive"))
    )
    (net (code "52") (name "Net-(R10-Pad2)") (class "Default")
      (node (ref "R10") (pin "2") (pinfunction "2_2") (pintype "passive"))
      (node (ref "TR2") (pin "2") (pinfunction "2_2") (pintype "passive"))
    )
    (net (code "53") (name "Net-(T1A-B)") (class "Default")
      (node (ref "T1") (pin "2") (pinfunction "B_2") (pintype "bidirectional"))
      (node (ref "TR1") (pin "2") (pinfunction "2_2") (pintype "passive"))
    )
    (net (code "54") (name "Net-(T1A-E)") (class "Default")
      (node (ref "R7") (pin "2") (pinfunction "2_2") (pintype "passive"))
      (node (ref "T1") (pin "4") (pinfunction "E_4") (pintype "bidirectional"))
      (node (ref "T1") (pin "5") (pinfunction "E_5") (pintype "bidirectional"))
    )
    (net (code "55") (name "Net-(T1B-C)") (class "Default")
      (node (ref "R11") (pin "2") (pinfunction "2_2") (pintype "passive"))
      (node (ref "R20") (pin "2") (pinfunction "2_2") (pintype "passive"))
      (node (ref "R28") (pin "2") (pinfunction "2_2") (pintype "passive"))
      (node (ref "R42") (pin "2") (pinfunction "2_2") (pintype "passive"))
      (node (ref "T1") (pin "6") (pinfunction "C_6") (pintype "bidirectional"))
    )
    (net (code "56") (name "unconnected-(2POLE-SWITCH-PadNORM)") (class "Default")
      (node (ref "2POLE") (pin "NORM") (pinfunction "SWITCH_NORM") (pintype "passive"))
    )
    (net (code "57") (name "unconnected-(4POLE-SWITCH-PadNORM)") (class "Default")
      (node (ref "4POLE") (pin "NORM") (pinfunction "SWITCH_NORM") (pintype "passive"))
    )
    (net (code "58") (name "unconnected-(IC1A-D-BIAS-Pad2)") (class "Default")
      (node (ref "IC1") (pin "2") (pinfunction "D-BIAS_2") (pintype "bidirectional"))
    )
    (net (code "59") (name "unconnected-(IC1B-D-BIAS-Pad15)") (class "Default")
      (node (ref "IC1") (pin "15") (pinfunction "D-BIAS_15") (pintype "bidirectional"))
    )
    (net (code "60") (name "unconnected-(IC2A-D-BIAS-Pad2)") (class "Default")
      (node (ref "IC2") (pin "2") (pinfunction "D-BIAS_2") (pintype "bidirectional"))
    )
    (net (code "61") (name "unconnected-(IC2B-D-BIAS-Pad15)") (class "Default")
      (node (ref "IC2") (pin "15") (pinfunction "D-BIAS_15") (pintype "bidirectional"))
    )
    (net (code "62") (name "unconnected-(IN1-SWITCH-PadNORM)") (class "Default")
      (node (ref "IN1") (pin "NORM") (pinfunction "SWITCH_NORM") (pintype "passive"))
    )
    (net (code "63") (name "unconnected-(IN2-SWITCH-PadNORM)") (class "Default")
      (node (ref "IN2") (pin "NORM") (pinfunction "SWITCH_NORM") (pintype "passive"))
    )
  )
)
